# DE-180417_02.net
KiCad netlist of a schematic drawn in Altium Designer
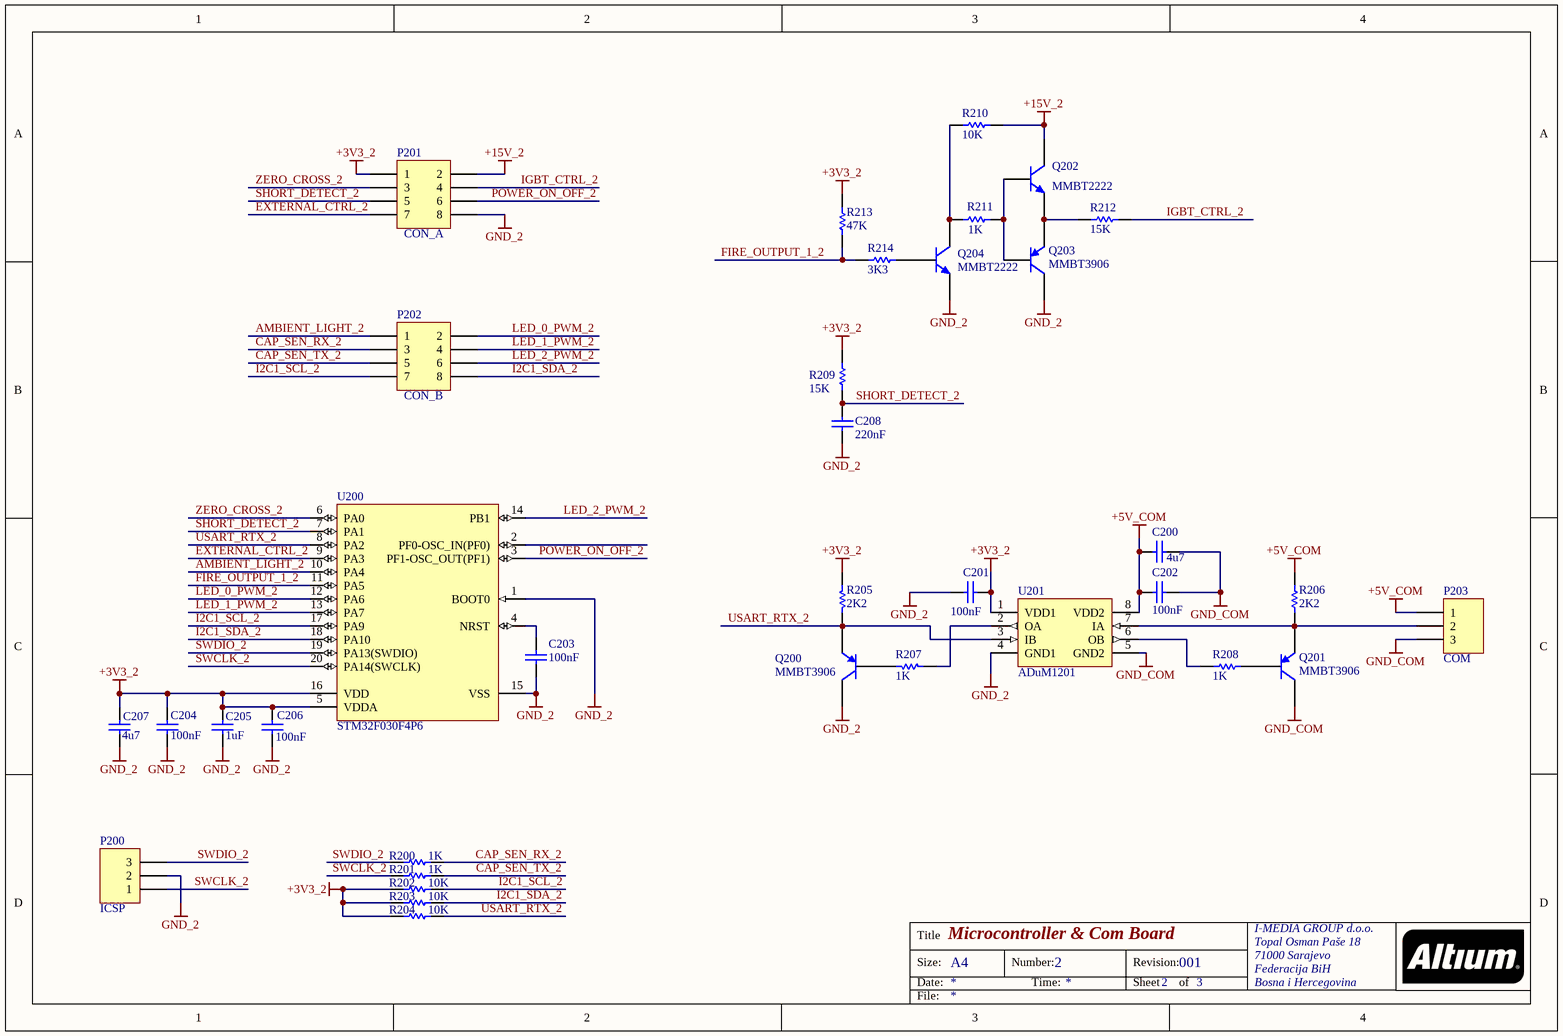
[diagram p0: DE-180417_02.SchDoc]

(export (version "E")
  (design (tool "Eeschema 10.0.6"))
  (components
    (comp (ref "C200")
      (value "4u7")
      (footprint "0805")
      (description "Ceramic Chip Capacitor - Standard")
      (fields (field (name "PUBLISHER") "Altium Limited"))
      (libsource (lib "KEMET Chip Capacitor") (part "C0805"))
    )
    (comp (ref "C201")
      (value "100nF")
      (footprint "0603")
      (description "Ceramic Chip Capacitor - Standard")
      (fields (field (name "PUBLISHER") "Altium Limited"))
      (libsource (lib "DE-180417") (part "C0603"))
    )
    (comp (ref "C202")
      (value "100nF")
      (footprint "0603")
      (description "Ceramic Chip Capacitor - Standard")
      (fields (field (name "PUBLISHER") "Altium Limited"))
      (libsource (lib "DE-180417") (part "C0603"))
    )
    (comp (ref "C203")
      (value "100nF")
      (footprint "0603")
      (description "Ceramic Chip Capacitor - Standard")
      (fields (field (name "PUBLISHER") "Altium Limited"))
      (libsource (lib "KEMET Chip Capacitor") (part "C0603"))
    )
    (comp (ref "C204")
      (value "100nF")
      (footprint "0603")
      (description "Ceramic Chip Capacitor - Standard")
      (fields (field (name "PUBLISHER") "Altium Limited"))
      (libsource (lib "KEMET Chip Capacitor") (part "C0603"))
    )
    (comp (ref "C205")
      (value "1uF")
      (footprint "0603")
      (description "Ceramic Chip Capacitor - Standard")
      (fields (field (name "PUBLISHER") "Altium Limited"))
      (libsource (lib "KEMET Chip Capacitor") (part "C0603"))
    )
    (comp (ref "C206")
      (value "100nF")
      (footprint "0603")
      (description "Ceramic Chip Capacitor - Standard")
      (fields (field (name "PUBLISHER") "Altium Limited"))
      (libsource (lib "KEMET Chip Capacitor") (part "C0603"))
    )
    (comp (ref "C207")
      (value "4u7")
      (footprint "0805")
      (description "Ceramic Chip Capacitor - Standard")
      (fields (field (name "PUBLISHER") "Altium Limited"))
      (libsource (lib "KEMET Chip Capacitor") (part "C0805"))
    )
    (comp (ref "C208")
      (value "220nF")
      (footprint "0603")
      (description "Ceramic Chip Capacitor - Standard")
      (fields (field (name "PUBLISHER") "Altium Limited"))
      (libsource (lib "DE-180417") (part "C0603"))
    )
    (comp (ref "P200")
      (value "ICSP")
      (footprint "HDR1X3")
      (description "Header, 3-Pin")
      (fields (field (name "PUBLISHER") "Altium Limited"))
      (libsource (lib "") (part "Header 3_1"))
    )
    (comp (ref "P201")
      (value "CON_A")
      (footprint "HDR2X4")
      (description "Header, 4-Pin, Dual row")
      (fields (field (name "PUBLISHER") "Altium Limited"))
      (libsource (lib "Miscellaneous Connectors") (part "Header 4X2"))
    )
    (comp (ref "P202")
      (value "CON_B")
      (footprint "HDR2X4")
      (description "Header, 4-Pin, Dual row")
      (fields (field (name "PUBLISHER") "Altium Limited"))
      (libsource (lib "Miscellaneous Connectors") (part "Header 4X2"))
    )
    (comp (ref "P203")
      (value "COM")
      (footprint "HDR1X3")
      (description "Header, 3-Pin")
      (fields (field (name "PUBLISHER") "Altium Limited"))
      (libsource (lib "Miscellaneous Connectors") (part "Header 3"))
    )
    (comp (ref "Q200")
      (value "MMBT3906")
      (footprint "SOT23_N")
      (description "PNP General-purpose Transistor")
      (fields (field (name "PUBLISHER") "Altium Limited"))
      (libsource (lib "DE-180417") (part "BC807"))
    )
    (comp (ref "Q201")
      (value "MMBT3906")
      (footprint "SOT23_N")
      (description "PNP General-purpose Transistor")
      (fields (field (name "PUBLISHER") "Altium Limited"))
      (libsource (lib "DE-180417") (part "BC807"))
    )
    (comp (ref "Q202")
      (value "MMBT2222")
      (footprint "SOT23_N")
      (description "NPN General-purpose Transistor")
      (fields (field (name "PUBLISHER") "Altium Limited"))
      (libsource (lib "DE-180417") (part "BC817"))
    )
    (comp (ref "Q203")
      (value "MMBT3906")
      (footprint "SOT23_N")
      (description "PNP General-purpose Transistor")
      (fields (field (name "PUBLISHER") "Altium Limited"))
      (libsource (lib "DE-180417") (part "BC807"))
    )
    (comp (ref "Q204")
      (value "MMBT2222")
      (footprint "SOT23_N")
      (description "NPN General-purpose Transistor")
      (fields (field (name "PUBLISHER") "Altium Limited"))
      (libsource (lib "DE-180417") (part "BC817"))
    )
    (comp (ref "R200")
      (value "1K")
      (footprint "ERA-0603")
      (fields (field (name "PUBLISHER") "Altium Limited"))
      (libsource (lib "DE-180417") (part "ERAV"))
    )
    (comp (ref "R201")
      (value "1K")
      (footprint "ERA-0603")
      (fields (field (name "PUBLISHER") "Altium Limited"))
      (libsource (lib "DE-180417") (part "ERAV"))
    )
    (comp (ref "R202")
      (value "10K")
      (footprint "ERA-0603")
      (fields (field (name "PUBLISHER") "Altium Limited"))
      (libsource (lib "DE-180417") (part "ERAV"))
    )
    (comp (ref "R203")
      (value "10K")
      (footprint "ERA-0603")
      (fields (field (name "PUBLISHER") "Altium Limited"))
      (libsource (lib "DE-180417") (part "ERAV"))
    )
    (comp (ref "R204")
      (value "10K")
      (footprint "ERA-0603")
      (fields (field (name "PUBLISHER") "Altium Limited"))
      (libsource (lib "DE-180417") (part "ERAV"))
    )
    (comp (ref "R205")
      (value "2K2")
      (footprint "ERA-0603")
      (fields (field (name "PUBLISHER") "Altium Limited"))
      (libsource (lib "DE-180417") (part "ERAV"))
    )
    (comp (ref "R206")
      (value "2K2")
      (footprint "ERA-0603")
      (fields (field (name "PUBLISHER") "Altium Limited"))
      (libsource (lib "DE-180417") (part "ERAV"))
    )
    (comp (ref "R207")
      (value "1K")
      (footprint "ERA-0603")
      (fields (field (name "PUBLISHER") "Altium Limited"))
      (libsource (lib "DE-180417") (part "ERAV"))
    )
    (comp (ref "R208")
      (value "1K")
      (footprint "ERA-0603")
      (fields (field (name "PUBLISHER") "Altium Limited"))
      (libsource (lib "DE-180417") (part "ERAV"))
    )
    (comp (ref "R209")
      (value "15K")
      (footprint "ERA-0603")
      (fields (field (name "PUBLISHER") "Altium Limited"))
      (libsource (lib "DE-180417") (part "ERAV"))
    )
    (comp (ref "R210")
      (value "10K")
      (footprint "ERA-0603")
      (fields (field (name "PUBLISHER") "Altium Limited"))
      (libsource (lib "DE-180417") (part "ERAV"))
    )
    (comp (ref "R211")
      (value "1K")
      (footprint "ERA-0603")
      (fields (field (name "PUBLISHER") "Altium Limited"))
      (libsource (lib "DE-180417") (part "ERAV"))
    )
    (comp (ref "R212")
      (value "15K")
      (footprint "ERA-0603")
      (fields (field (name "PUBLISHER") "Altium Limited"))
      (libsource (lib "DE-180417") (part "ERAV"))
    )
    (comp (ref "R213")
      (value "47K")
      (footprint "ERA-0603")
      (fields (field (name "PUBLISHER") "Altium Limited"))
      (libsource (lib "DE-180417") (part "ERAV"))
    )
    (comp (ref "R214")
      (value "3K3")
      (footprint "ERA-0603")
      (fields (field (name "PUBLISHER") "Altium Limited"))
      (libsource (lib "DE-180417") (part "ERAV"))
    )
    (comp (ref "U200")
      (value "STM32F030F4P6")
      (footprint "STM-TSSOP20_N")
      (libsource (lib "STMicroelectronics STM32 F0") (part "STM32F030F4P6"))
    )
    (comp (ref "U201")
      (value "ADuM1201")
      (footprint "SOP8")
      (description "Digital Isolator")
      (libsource (lib "DE-180417") (part "ADuM1201"))
    )
  )
  (nets
    (net (code "1") (name "+3V3_2") (class "Default")
      (node (ref "C201") (pin "1") (pinfunction "1_1") (pintype "passive"))
      (node (ref "C204") (pin "1") (pinfunction "1_1") (pintype "passive"))
      (node (ref "C205") (pin "1") (pinfunction "1_1") (pintype "passive"))
      (node (ref "C206") (pin "1") (pinfunction "1_1") (pintype "passive"))
      (node (ref "C207") (pin "1") (pinfunction "1_1") (pintype "passive"))
      (node (ref "P201") (pin "1") (pinfunction "1_1") (pintype "passive"))
      (node (ref "R202") (pin "2") (pinfunction "2_2") (pintype "passive"))
      (node (ref "R203") (pin "2") (pinfunction "2_2") (pintype "passive"))
      (node (ref "R204") (pin "2") (pinfunction "2_2") (pintype "passive"))
      (node (ref "R205") (pin "1") (pinfunction "1_1") (pintype "passive"))
      (node (ref "R209") (pin "2") (pinfunction "2_2") (pintype "passive"))
      (node (ref "R213") (pin "1") (pinfunction "1_1") (pintype "passive"))
      (node (ref "U200") (pin "16") (pinfunction "VDD_16") (pintype "power_in"))
      (node (ref "U200") (pin "5") (pinfunction "VDDA_5") (pintype "power_in"))
      (node (ref "U201") (pin "1") (pinfunction "VDD1_1") (pintype "power_in"))
    )
    (net (code "2") (name "+5V_COM") (class "Default")
      (node (ref "C200") (pin "1") (pinfunction "1_1") (pintype "passive"))
      (node (ref "C202") (pin "1") (pinfunction "1_1") (pintype "passive"))
      (node (ref "P203") (pin "1") (pinfunction "1_1") (pintype "passive"))
      (node (ref "R206") (pin "1") (pinfunction "1_1") (pintype "passive"))
      (node (ref "U201") (pin "8") (pinfunction "VDD2_8") (pintype "power_in"))
    )
    (net (code "3") (name "+15V_2") (class "Default")
      (node (ref "P201") (pin "2") (pinfunction "2_2") (pintype "passive"))
      (node (ref "Q202") (pin "3") (pinfunction "C_3") (pintype "passive"))
      (node (ref "R210") (pin "1") (pinfunction "1_1") (pintype "passive"))
    )
    (net (code "4") (name "/AMBIENT_LIGHT_2") (class "Default")
      (node (ref "P202") (pin "1") (pinfunction "1_1") (pintype "passive"))
      (node (ref "U200") (pin "10") (pinfunction "PA4_10") (pintype "bidirectional"))
    )
    (net (code "5") (name "/CAP_SEN_RX_2") (class "Default")
      (node (ref "P202") (pin "3") (pinfunction "3_3") (pintype "passive"))
      (node (ref "R200") (pin "1") (pinfunction "1_1") (pintype "passive"))
    )
    (net (code "6") (name "/CAP_SEN_TX_2") (class "Default")
      (node (ref "P202") (pin "5") (pinfunction "5_5") (pintype "passive"))
      (node (ref "R201") (pin "1") (pinfunction "1_1") (pintype "passive"))
    )
    (net (code "7") (name "/EXTERNAL_CTRL_2") (class "Default")
      (node (ref "P201") (pin "7") (pinfunction "7_7") (pintype "passive"))
      (node (ref "U200") (pin "9") (pinfunction "PA3_9") (pintype "bidirectional"))
    )
    (net (code "8") (name "/FIRE_OUTPUT_1_2") (class "Default")
      (node (ref "R213") (pin "2") (pinfunction "2_2") (pintype "passive"))
      (node (ref "R214") (pin "2") (pinfunction "2_2") (pintype "passive"))
      (node (ref "U200") (pin "11") (pinfunction "PA5_11") (pintype "bidirectional"))
    )
    (net (code "9") (name "/I2C1_SCL_2") (class "Default")
      (node (ref "P202") (pin "7") (pinfunction "7_7") (pintype "passive"))
      (node (ref "R202") (pin "1") (pinfunction "1_1") (pintype "passive"))
      (node (ref "U200") (pin "17") (pinfunction "PA9_17") (pintype "bidirectional"))
    )
    (net (code "10") (name "/I2C1_SDA_2") (class "Default")
      (node (ref "P202") (pin "8") (pinfunction "8_8") (pintype "passive"))
      (node (ref "R203") (pin "1") (pinfunction "1_1") (pintype "passive"))
      (node (ref "U200") (pin "18") (pinfunction "PA10_18") (pintype "bidirectional"))
    )
    (net (code "11") (name "/IGBT_CTRL_2") (class "Default")
      (node (ref "P201") (pin "4") (pinfunction "4_4") (pintype "passive"))
      (node (ref "R212") (pin "2") (pinfunction "2_2") (pintype "passive"))
    )
    (net (code "12") (name "/LED_0_PWM_2") (class "Default")
      (node (ref "P202") (pin "2") (pinfunction "2_2") (pintype "passive"))
      (node (ref "U200") (pin "12") (pinfunction "PA6_12") (pintype "bidirectional"))
    )
    (net (code "13") (name "/LED_1_PWM_2") (class "Default")
      (node (ref "P202") (pin "4") (pinfunction "4_4") (pintype "passive"))
      (node (ref "U200") (pin "13") (pinfunction "PA7_13") (pintype "bidirectional"))
    )
    (net (code "14") (name "/LED_2_PWM_2") (class "Default")
      (node (ref "P202") (pin "6") (pinfunction "6_6") (pintype "passive"))
      (node (ref "U200") (pin "14") (pinfunction "PB1_14") (pintype "bidirectional"))
    )
    (net (code "15") (name "/POWER_ON_OFF_2") (class "Default")
      (node (ref "P201") (pin "6") (pinfunction "6_6") (pintype "passive"))
      (node (ref "U200") (pin "3") (pinfunction "PF1-OSC_OUT(PF1)_3") (pintype "bidirectional"))
    )
    (net (code "16") (name "/SHORT_DETECT_2") (class "Default")
      (node (ref "C208") (pin "2") (pinfunction "2_2") (pintype "passive"))
      (node (ref "P201") (pin "5") (pinfunction "5_5") (pintype "passive"))
      (node (ref "R209") (pin "1") (pinfunction "1_1") (pintype "passive"))
      (node (ref "U200") (pin "7") (pinfunction "PA1_7") (pintype "bidirectional"))
    )
    (net (code "17") (name "/SWCLK_2") (class "Default")
      (node (ref "P200") (pin "1") (pinfunction "1_1") (pintype "passive"))
      (node (ref "R201") (pin "2") (pinfunction "2_2") (pintype "passive"))
      (node (ref "U200") (pin "20") (pinfunction "PA14(SWCLK)_20") (pintype "bidirectional"))
    )
    (net (code "18") (name "/SWDIO_2") (class "Default")
      (node (ref "P200") (pin "3") (pinfunction "3_3") (pintype "passive"))
      (node (ref "R200") (pin "2") (pinfunction "2_2") (pintype "passive"))
      (node (ref "U200") (pin "19") (pinfunction "PA13(SWDIO)_19") (pintype "bidirectional"))
    )
    (net (code "19") (name "/USART_RTX_2") (class "Default")
      (node (ref "Q200") (pin "2") (pinfunction "E_2") (pintype "passive"))
      (node (ref "R204") (pin "1") (pinfunction "1_1") (pintype "passive"))
      (node (ref "R205") (pin "2") (pinfunction "2_2") (pintype "passive"))
      (node (ref "U200") (pin "8") (pinfunction "PA2_8") (pintype "bidirectional"))
      (node (ref "U201") (pin "3") (pinfunction "IB_3") (pintype "input"))
    )
    (net (code "20") (name "/ZERO_CROSS_2") (class "Default")
      (node (ref "P201") (pin "3") (pinfunction "3_3") (pintype "passive"))
      (node (ref "U200") (pin "6") (pinfunction "PA0_6") (pintype "bidirectional"))
    )
    (net (code "21") (name "GND_2") (class "Default")
      (node (ref "C201") (pin "2") (pinfunction "2_2") (pintype "passive"))
      (node (ref "C203") (pin "2") (pinfunction "2_2") (pintype "passive"))
      (node (ref "C204") (pin "2") (pinfunction "2_2") (pintype "passive"))
      (node (ref "C205") (pin "2") (pinfunction "2_2") (pintype "passive"))
      (node (ref "C206") (pin "2") (pinfunction "2_2") (pintype "passive"))
      (node (ref "C207") (pin "2") (pinfunction "2_2") (pintype "passive"))
      (node (ref "C208") (pin "1") (pinfunction "1_1") (pintype "passive"))
      (node (ref "P200") (pin "2") (pinfunction "2_2") (pintype "passive"))
      (node (ref "P201") (pin "8") (pinfunction "8_8") (pintype "passive"))
      (node (ref "Q200") (pin "3") (pinfunction "C_3") (pintype "passive"))
      (node (ref "Q203") (pin "3") (pinfunction "C_3") (pintype "passive"))
      (node (ref "Q204") (pin "2") (pinfunction "E_2") (pintype "passive"))
      (node (ref "U200") (pin "1") (pinfunction "BOOT0_1") (pintype "input"))
      (node (ref "U200") (pin "15") (pinfunction "VSS_15") (pintype "power_in"))
      (node (ref "U201") (pin "4") (pinfunction "GND1_4") (pintype "power_in"))
    )
    (net (code "22") (name "GND_COM") (class "Default")
      (node (ref "C200") (pin "2") (pinfunction "2_2") (pintype "passive"))
      (node (ref "C202") (pin "2") (pinfunction "2_2") (pintype "passive"))
      (node (ref "P203") (pin "3") (pinfunction "3_3") (pintype "passive"))
      (node (ref "Q201") (pin "3") (pinfunction "C_3") (pintype "passive"))
      (node (ref "U201") (pin "5") (pinfunction "GND2_5") (pintype "power_in"))
    )
    (net (code "23") (name "Net-(Q200-B)") (class "Default")
      (node (ref "Q200") (pin "1") (pinfunction "B_1") (pintype "passive"))
      (node (ref "R207") (pin "1") (pinfunction "1_1") (pintype "passive"))
    )
    (net (code "24") (name "Net-(Q201-B)") (class "Default")
      (node (ref "Q201") (pin "1") (pinfunction "B_1") (pintype "passive"))
      (node (ref "R208") (pin "1") (pinfunction "1_1") (pintype "passive"))
    )
    (net (code "25") (name "Net-(Q201-E)") (class "Default")
      (node (ref "P203") (pin "2") (pinfunction "2_2") (pintype "passive"))
      (node (ref "Q201") (pin "2") (pinfunction "E_2") (pintype "passive"))
      (node (ref "R206") (pin "2") (pinfunction "2_2") (pintype "passive"))
      (node (ref "U201") (pin "7") (pinfunction "IA_7") (pintype "input"))
    )
    (net (code "26") (name "Net-(Q202-B)") (class "Default")
      (node (ref "Q202") (pin "1") (pinfunction "B_1") (pintype "passive"))
      (node (ref "Q203") (pin "1") (pinfunction "B_1") (pintype "passive"))
      (node (ref "R211") (pin "1") (pinfunction "1_1") (pintype "passive"))
    )
    (net (code "27") (name "Net-(Q202-E)") (class "Default")
      (node (ref "Q202") (pin "2") (pinfunction "E_2") (pintype "passive"))
      (node (ref "Q203") (pin "2") (pinfunction "E_2") (pintype "passive"))
      (node (ref "R212") (pin "1") (pinfunction "1_1") (pintype "passive"))
    )
    (net (code "28") (name "Net-(Q204-B)") (class "Default")
      (node (ref "Q204") (pin "1") (pinfunction "B_1") (pintype "passive"))
      (node (ref "R214") (pin "1") (pinfunction "1_1") (pintype "passive"))
    )
    (net (code "29") (name "Net-(Q204-C)") (class "Default")
      (node (ref "Q204") (pin "3") (pinfunction "C_3") (pintype "passive"))
      (node (ref "R210") (pin "2") (pinfunction "2_2") (pintype "passive"))
      (node (ref "R211") (pin "2") (pinfunction "2_2") (pintype "passive"))
    )
    (net (code "30") (name "Net-(U200-NRST)") (class "Default")
      (node (ref "C203") (pin "1") (pinfunction "1_1") (pintype "passive"))
      (node (ref "U200") (pin "4") (pinfunction "NRST_4") (pintype "bidirectional"))
    )
    (net (code "31") (name "Net-(U201-OA)") (class "Default")
      (node (ref "R207") (pin "2") (pinfunction "2_2") (pintype "passive"))
      (node (ref "U201") (pin "2") (pinfunction "OA_2") (pintype "output"))
    )
    (net (code "32") (name "Net-(U201-OB)") (class "Default")
      (node (ref "R208") (pin "2") (pinfunction "2_2") (pintype "passive"))
      (node (ref "U201") (pin "6") (pinfunction "OB_6") (pintype "output"))
    )
    (net (code "33") (name "unconnected-(U200-PF0-OSC_IN(PF0)-Pad2)") (class "Default")
      (node (ref "U200") (pin "2") (pinfunction "PF0-OSC_IN(PF0)_2") (pintype "bidirectional"))
    )
  )
)
